# sram.net
KiCad netlist of a schematic drawn in Altium Designer
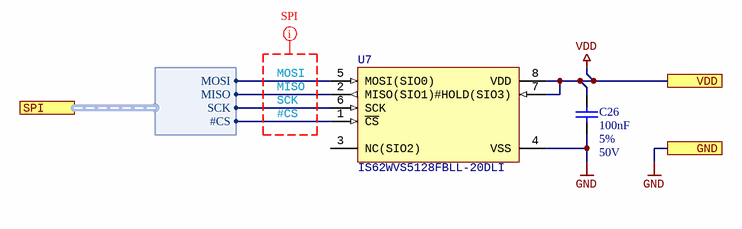
[diagram p0: sram.SchDoc]

(export (version "E")
  (design (tool "Eeschema 10.0.6"))
  (components
    (comp (ref "C26")
      (value "100nF")
      (footprint "CAPC1608N")
      (description "Capacitor")
      (fields (field (name "TOLERANCE") "5%") (field (name "VOLTAGE") "50V"))
      (libsource (lib "passives") (part "Capacitor"))
    )
    (comp (ref "U7")
      (value "IS62WVS5128FBLL-20DLI")
      (footprint "SO-8_L")
      (description "512Kx8 LOW VOLTAGE, SERIAL SRAM with SPI, SDI and SQI INTERFACE")
      (libsource (lib "mem") (part "IS62WVS5128FBLL-20xLI"))
    )
  )
  (nets
    (net (code "2") (name "/#CS") (class "Default")
      (node (ref "U7") (pin "1") (pinfunction "~{CS}_1") (pintype "input"))
    )
    (net (code "3") (name "/MISO") (class "Default")
      (node (ref "U7") (pin "2") (pinfunction "MISO(SIO1)_2") (pintype "output"))
    )
    (net (code "4") (name "/MOSI") (class "Default")
      (node (ref "U7") (pin "5") (pinfunction "MOSI(SIO0)_5") (pintype "input"))
    )
    (net (code "5") (name "/SCK") (class "Default")
      (node (ref "U7") (pin "6") (pinfunction "SCK_6") (pintype "input"))
    )
    (net (code "7") (name "GND") (class "Default")
      (node (ref "C26") (pin "1") (pinfunction "1_1") (pintype "passive"))
      (node (ref "U7") (pin "4") (pinfunction "VSS_4") (pintype "power_in"))
    )
    (net (code "8") (name "VDD") (class "Default")
      (node (ref "C26") (pin "2") (pinfunction "2_2") (pintype "passive"))
      (node (ref "U7") (pin "7") (pinfunction "#HOLD(SIO3)_7") (pintype "input"))
      (node (ref "U7") (pin "8") (pinfunction "VDD_8") (pintype "power_in"))
    )
    (net (code "9") (name "unconnected-(U7-NC(SIO2)-Pad3)") (class "Default")
      (node (ref "U7") (pin "3") (pinfunction "NC(SIO2)_3") (pintype "passive"))
    )
    (net (code "10") (name "unconnected-(U7-NC-Pad3)") (class "Default")
      (node (ref "U7") (pin "3") (pinfunction "NC_3") (pintype "passive"))
    )
  )
)
